# BV100011_ControlConnector.net
KiCad netlist of a schematic drawn in Altium Designer
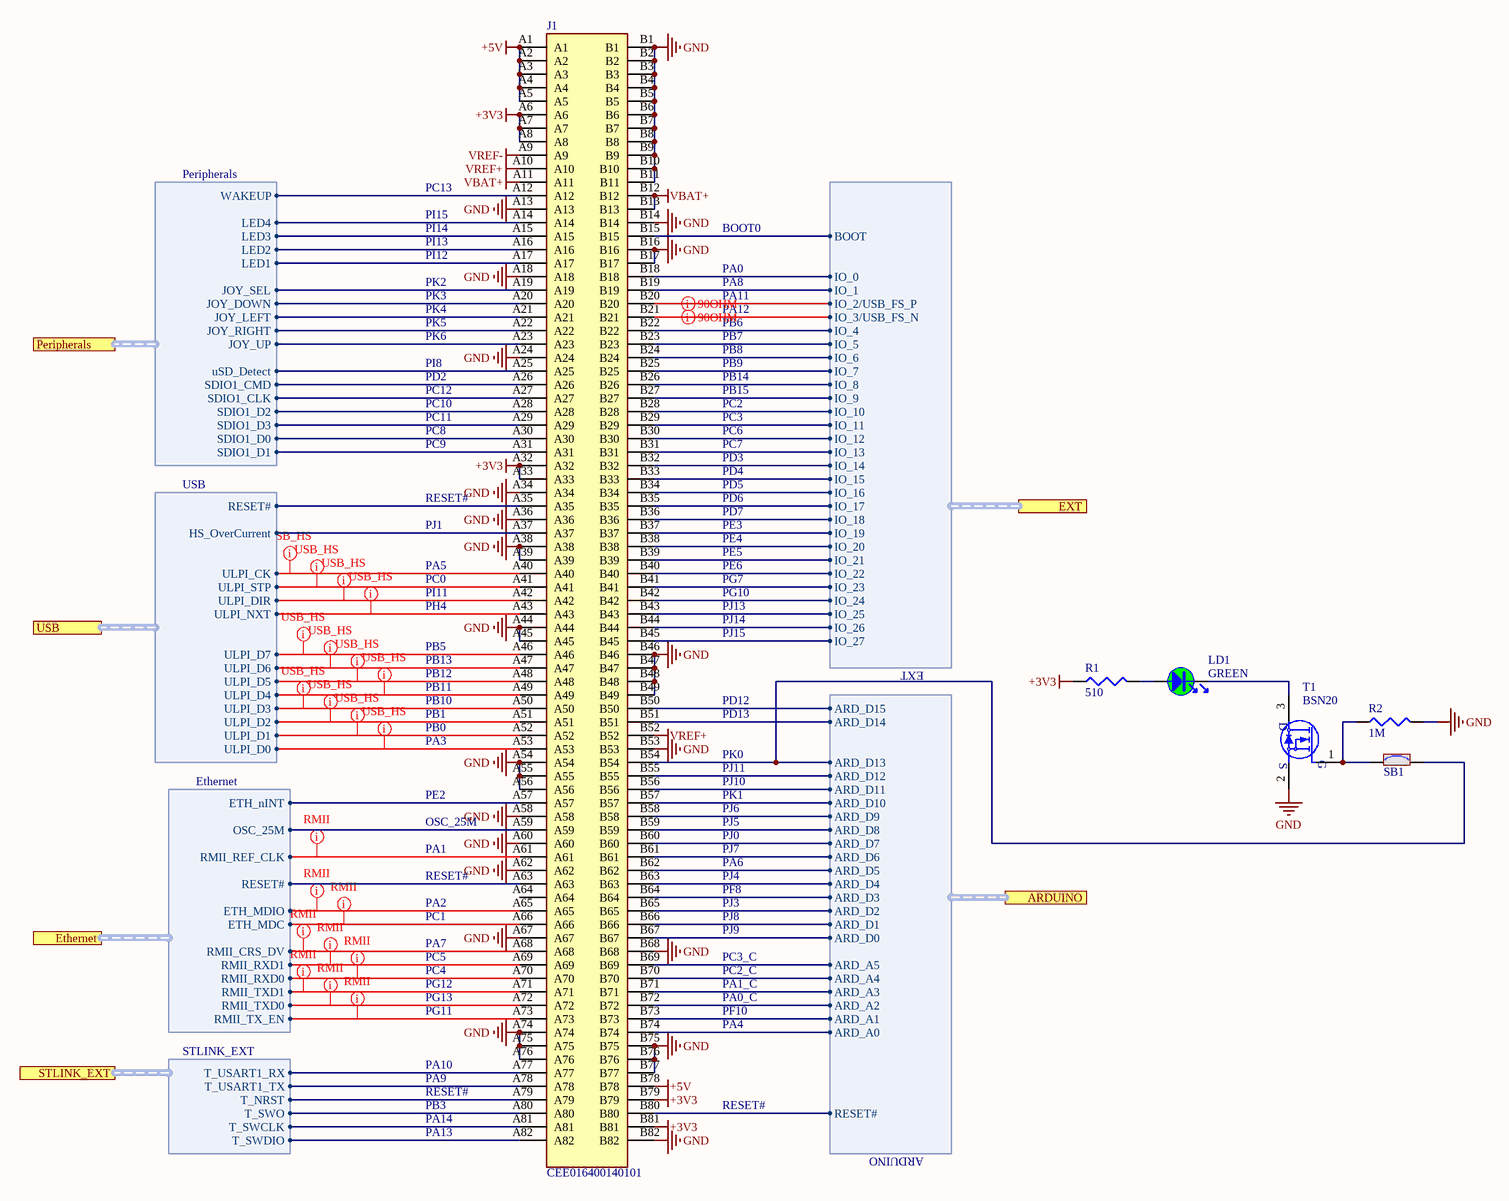
[diagram p0: BV100011_ControlConnector.SchDoc]

(export (version "E")
  (design (tool "Eeschema 10.0.6"))
  (components
    (comp (ref "J1")
      (value "CEE016400140101")
      (footprint "CEE016400140101-M")
      (description "Connector")
      (fields (field (name "MOUSER PART NUMBER") "523-CEE016400140101"))
      (libsource (lib "PCIE-164-02-F-D-RA") (part "CEE016400140101"))
    )
    (comp (ref "LD1")
      (value "GREEN")
      (footprint "LED_0603_GREEN")
      (description "LED, Green, 0603")
      (fields
        (field (name "INTERNAL_PART_NUMBER") "MCD-00050")
        (field (name "MANUFACTURER_PART_NUMBER") "19-213SYGC/S530-E2/TR8")
        (field (name "PROVIDED_BY") "Subcon")
      )
      (libsource (lib "MCD_PARTS_database") (part "LED_green"))
    )
    (comp (ref "R1")
      (value "510")
      (footprint "R0603")
      (description "Resistor")
      (fields (field (name "PUBLISHER") "Altium Limited"))
      (libsource (lib "Miscellaneous Devices") (part "Res3"))
    )
    (comp (ref "R2")
      (value "1M")
      (footprint "R0603")
      (description "Resistor")
      (fields (field (name "PUBLISHER") "Altium Limited"))
      (libsource (lib "Miscellaneous Devices") (part "Res3"))
    )
    (comp (ref "SB1")
      (value "SB_ON")
      (footprint "SB_0603")
      (description "Solder Bridge ON")
      (fields
        (field (name "INTERNAL_PART_NUMBER") "MCD-00071")
        (field (name "MANUFACTURER_PART_NUMBER") "RC0603JR-070RL")
        (field (name "PROVIDED_BY") "SUBCO")
      )
      (libsource (lib "MB1364") (part "MCD-00071"))
    )
    (comp (ref "T1")
      (value "BSN20")
      (footprint "MOS_SOT23")
      (description "N-channel enhancement mode field-effect transistor")
      (fields
        (field (name "INTERNAL_PART_NUMBER") "MCD-00151")
        (field (name "MANUFACTURER") "NXP")
        (field (name "PROVIDED_BY") "Subcon")
      )
      (libsource (lib "MCD_PARTS_database") (part "BSN20"))
    )
  )
  (nets
    (net (code "7") (name "+3V3") (class "Default")
      (node (ref "J1") (pin "A32") (pinfunction "A32_A32") (pintype "passive"))
      (node (ref "J1") (pin "A33") (pinfunction "A33_A33") (pintype "passive"))
      (node (ref "J1") (pin "A6") (pinfunction "A6_A6") (pintype "passive"))
      (node (ref "J1") (pin "A7") (pinfunction "A7_A7") (pintype "passive"))
      (node (ref "J1") (pin "A8") (pinfunction "A8_A8") (pintype "passive"))
      (node (ref "J1") (pin "B79") (pinfunction "B79_B79") (pintype "passive"))
      (node (ref "J1") (pin "B81") (pinfunction "B81_B81") (pintype "passive"))
      (node (ref "R1") (pin "1") (pinfunction "1_1") (pintype "passive"))
    )
    (net (code "8") (name "+5V") (class "Default")
      (node (ref "J1") (pin "A1") (pinfunction "A1_A1") (pintype "passive"))
      (node (ref "J1") (pin "A2") (pinfunction "A2_A2") (pintype "passive"))
      (node (ref "J1") (pin "A3") (pinfunction "A3_A3") (pintype "passive"))
      (node (ref "J1") (pin "A4") (pinfunction "A4_A4") (pintype "passive"))
      (node (ref "J1") (pin "A5") (pinfunction "A5_A5") (pintype "passive"))
      (node (ref "J1") (pin "B78") (pinfunction "B78_B78") (pintype "passive"))
    )
    (net (code "9") (name "/ARD_A0") (class "Default")
      (node (ref "J1") (pin "B74") (pinfunction "B74_B74") (pintype "passive"))
    )
    (net (code "10") (name "/ARD_A1") (class "Default")
      (node (ref "J1") (pin "B73") (pinfunction "B73_B73") (pintype "passive"))
    )
    (net (code "11") (name "/ARD_A2") (class "Default")
      (node (ref "J1") (pin "B72") (pinfunction "B72_B72") (pintype "passive"))
    )
    (net (code "12") (name "/ARD_A3") (class "Default")
      (node (ref "J1") (pin "B71") (pinfunction "B71_B71") (pintype "passive"))
    )
    (net (code "13") (name "/ARD_A4") (class "Default")
      (node (ref "J1") (pin "B70") (pinfunction "B70_B70") (pintype "passive"))
    )
    (net (code "14") (name "/ARD_A5") (class "Default")
      (node (ref "J1") (pin "B69") (pinfunction "B69_B69") (pintype "passive"))
    )
    (net (code "15") (name "/ARD_D0") (class "Default")
      (node (ref "J1") (pin "B67") (pinfunction "B67_B67") (pintype "passive"))
    )
    (net (code "16") (name "/ARD_D1") (class "Default")
      (node (ref "J1") (pin "B66") (pinfunction "B66_B66") (pintype "passive"))
    )
    (net (code "17") (name "/ARD_D2") (class "Default")
      (node (ref "J1") (pin "B65") (pinfunction "B65_B65") (pintype "passive"))
    )
    (net (code "18") (name "/ARD_D3") (class "Default")
      (node (ref "J1") (pin "B64") (pinfunction "B64_B64") (pintype "passive"))
    )
    (net (code "19") (name "/ARD_D4") (class "Default")
      (node (ref "J1") (pin "B63") (pinfunction "B63_B63") (pintype "passive"))
    )
    (net (code "20") (name "/ARD_D5") (class "Default")
      (node (ref "J1") (pin "B62") (pinfunction "B62_B62") (pintype "passive"))
    )
    (net (code "21") (name "/ARD_D6") (class "Default")
      (node (ref "J1") (pin "B61") (pinfunction "B61_B61") (pintype "passive"))
    )
    (net (code "22") (name "/ARD_D7") (class "Default")
      (node (ref "J1") (pin "B60") (pinfunction "B60_B60") (pintype "passive"))
    )
    (net (code "23") (name "/ARD_D8") (class "Default")
      (node (ref "J1") (pin "B59") (pinfunction "B59_B59") (pintype "passive"))
    )
    (net (code "24") (name "/ARD_D9") (class "Default")
      (node (ref "J1") (pin "B58") (pinfunction "B58_B58") (pintype "passive"))
    )
    (net (code "25") (name "/ARD_D10") (class "Default")
      (node (ref "J1") (pin "B57") (pinfunction "B57_B57") (pintype "passive"))
    )
    (net (code "26") (name "/ARD_D11") (class "Default")
      (node (ref "J1") (pin "B56") (pinfunction "B56_B56") (pintype "passive"))
    )
    (net (code "27") (name "/ARD_D12") (class "Default")
      (node (ref "J1") (pin "B55") (pinfunction "B55_B55") (pintype "passive"))
    )
    (net (code "28") (name "/ARD_D13") (class "Default")
      (node (ref "J1") (pin "B54") (pinfunction "B54_B54") (pintype "passive"))
      (node (ref "SB1") (pin "2") (pinfunction "2_2") (pintype "passive"))
    )
    (net (code "29") (name "/ARD_D14") (class "Default")
      (node (ref "J1") (pin "B51") (pinfunction "B51_B51") (pintype "passive"))
    )
    (net (code "30") (name "/ARD_D15") (class "Default")
      (node (ref "J1") (pin "B50") (pinfunction "B50_B50") (pintype "passive"))
    )
    (net (code "31") (name "/BOOT") (class "Default")
      (node (ref "J1") (pin "B15") (pinfunction "B15_B15") (pintype "passive"))
    )
    (net (code "32") (name "/ETH_MDC") (class "Default")
      (node (ref "J1") (pin "A66") (pinfunction "A66_A66") (pintype "passive"))
    )
    (net (code "33") (name "/ETH_MDIO") (class "Default")
      (node (ref "J1") (pin "A65") (pinfunction "A65_A65") (pintype "passive"))
    )
    (net (code "34") (name "/ETH_nINT") (class "Default")
      (node (ref "J1") (pin "A57") (pinfunction "A57_A57") (pintype "passive"))
    )
    (net (code "35") (name "/HS_OverCurrent") (class "Default")
      (node (ref "J1") (pin "A37") (pinfunction "A37_A37") (pintype "passive"))
    )
    (net (code "36") (name "/IO_0") (class "Default")
      (node (ref "J1") (pin "B18") (pinfunction "B18_B18") (pintype "passive"))
    )
    (net (code "37") (name "/IO_1") (class "Default")
      (node (ref "J1") (pin "B19") (pinfunction "B19_B19") (pintype "passive"))
    )
    (net (code "38") (name "/IO_2{slash}USB_FS_P") (class "Default")
      (node (ref "J1") (pin "B20") (pinfunction "B20_B20") (pintype "passive"))
    )
    (net (code "39") (name "/IO_3{slash}USB_FS_N") (class "Default")
      (node (ref "J1") (pin "B21") (pinfunction "B21_B21") (pintype "passive"))
    )
    (net (code "40") (name "/IO_4") (class "Default")
      (node (ref "J1") (pin "B22") (pinfunction "B22_B22") (pintype "passive"))
    )
    (net (code "41") (name "/IO_5") (class "Default")
      (node (ref "J1") (pin "B23") (pinfunction "B23_B23") (pintype "passive"))
    )
    (net (code "42") (name "/IO_6") (class "Default")
      (node (ref "J1") (pin "B24") (pinfunction "B24_B24") (pintype "passive"))
    )
    (net (code "43") (name "/IO_7") (class "Default")
      (node (ref "J1") (pin "B25") (pinfunction "B25_B25") (pintype "passive"))
    )
    (net (code "44") (name "/IO_8") (class "Default")
      (node (ref "J1") (pin "B26") (pinfunction "B26_B26") (pintype "passive"))
    )
    (net (code "45") (name "/IO_9") (class "Default")
      (node (ref "J1") (pin "B27") (pinfunction "B27_B27") (pintype "passive"))
    )
    (net (code "46") (name "/IO_10") (class "Default")
      (node (ref "J1") (pin "B28") (pinfunction "B28_B28") (pintype "passive"))
    )
    (net (code "47") (name "/IO_11") (class "Default")
      (node (ref "J1") (pin "B29") (pinfunction "B29_B29") (pintype "passive"))
    )
    (net (code "48") (name "/IO_12") (class "Default")
      (node (ref "J1") (pin "B30") (pinfunction "B30_B30") (pintype "passive"))
    )
    (net (code "49") (name "/IO_13") (class "Default")
      (node (ref "J1") (pin "B31") (pinfunction "B31_B31") (pintype "passive"))
    )
    (net (code "50") (name "/IO_14") (class "Default")
      (node (ref "J1") (pin "B32") (pinfunction "B32_B32") (pintype "passive"))
    )
    (net (code "51") (name "/IO_15") (class "Default")
      (node (ref "J1") (pin "B33") (pinfunction "B33_B33") (pintype "passive"))
    )
    (net (code "52") (name "/IO_16") (class "Default")
      (node (ref "J1") (pin "B34") (pinfunction "B34_B34") (pintype "passive"))
    )
    (net (code "53") (name "/IO_17") (class "Default")
      (node (ref "J1") (pin "B35") (pinfunction "B35_B35") (pintype "passive"))
    )
    (net (code "54") (name "/IO_18") (class "Default")
      (node (ref "J1") (pin "B36") (pinfunction "B36_B36") (pintype "passive"))
    )
    (net (code "55") (name "/IO_19") (class "Default")
      (node (ref "J1") (pin "B37") (pinfunction "B37_B37") (pintype "passive"))
    )
    (net (code "56") (name "/IO_20") (class "Default")
      (node (ref "J1") (pin "B38") (pinfunction "B38_B38") (pintype "passive"))
    )
    (net (code "57") (name "/IO_21") (class "Default")
      (node (ref "J1") (pin "B39") (pinfunction "B39_B39") (pintype "passive"))
    )
    (net (code "58") (name "/IO_22") (class "Default")
      (node (ref "J1") (pin "B40") (pinfunction "B40_B40") (pintype "passive"))
    )
    (net (code "59") (name "/IO_23") (class "Default")
      (node (ref "J1") (pin "B41") (pinfunction "B41_B41") (pintype "passive"))
    )
    (net (code "60") (name "/IO_24") (class "Default")
      (node (ref "J1") (pin "B42") (pinfunction "B42_B42") (pintype "passive"))
    )
    (net (code "61") (name "/IO_25") (class "Default")
      (node (ref "J1") (pin "B43") (pinfunction "B43_B43") (pintype "passive"))
    )
    (net (code "62") (name "/IO_26") (class "Default")
      (node (ref "J1") (pin "B44") (pinfunction "B44_B44") (pintype "passive"))
    )
    (net (code "63") (name "/IO_27") (class "Default")
      (node (ref "J1") (pin "B45") (pinfunction "B45_B45") (pintype "passive"))
    )
    (net (code "64") (name "/JOY_DOWN") (class "Default")
      (node (ref "J1") (pin "A20") (pinfunction "A20_A20") (pintype "passive"))
    )
    (net (code "65") (name "/JOY_LEFT") (class "Default")
      (node (ref "J1") (pin "A21") (pinfunction "A21_A21") (pintype "passive"))
    )
    (net (code "66") (name "/JOY_RIGHT") (class "Default")
      (node (ref "J1") (pin "A22") (pinfunction "A22_A22") (pintype "passive"))
    )
    (net (code "67") (name "/JOY_SEL") (class "Default")
      (node (ref "J1") (pin "A19") (pinfunction "A19_A19") (pintype "passive"))
    )
    (net (code "68") (name "/JOY_UP") (class "Default")
      (node (ref "J1") (pin "A23") (pinfunction "A23_A23") (pintype "passive"))
    )
    (net (code "69") (name "/LED1") (class "Default")
      (node (ref "J1") (pin "A17") (pinfunction "A17_A17") (pintype "passive"))
    )
    (net (code "70") (name "/LED2") (class "Default")
      (node (ref "J1") (pin "A16") (pinfunction "A16_A16") (pintype "passive"))
    )
    (net (code "71") (name "/LED3") (class "Default")
      (node (ref "J1") (pin "A15") (pinfunction "A15_A15") (pintype "passive"))
    )
    (net (code "72") (name "/LED4") (class "Default")
      (node (ref "J1") (pin "A14") (pinfunction "A14_A14") (pintype "passive"))
    )
    (net (code "73") (name "/OSC_25M") (class "Default")
      (node (ref "J1") (pin "A59") (pinfunction "A59_A59") (pintype "passive"))
    )
    (net (code "74") (name "/RMII_CRS_DV") (class "Default")
      (node (ref "J1") (pin "A68") (pinfunction "A68_A68") (pintype "passive"))
    )
    (net (code "75") (name "/RMII_REF_CLK") (class "Default")
      (node (ref "J1") (pin "A61") (pinfunction "A61_A61") (pintype "passive"))
    )
    (net (code "76") (name "/RMII_RXD0") (class "Default")
      (node (ref "J1") (pin "A70") (pinfunction "A70_A70") (pintype "passive"))
    )
    (net (code "77") (name "/RMII_RXD1") (class "Default")
      (node (ref "J1") (pin "A69") (pinfunction "A69_A69") (pintype "passive"))
    )
    (net (code "78") (name "/RMII_TXD0") (class "Default")
      (node (ref "J1") (pin "A72") (pinfunction "A72_A72") (pintype "passive"))
    )
    (net (code "79") (name "/RMII_TXD1") (class "Default")
      (node (ref "J1") (pin "A71") (pinfunction "A71_A71") (pintype "passive"))
    )
    (net (code "80") (name "/RMII_TX_EN") (class "Default")
      (node (ref "J1") (pin "A73") (pinfunction "A73_A73") (pintype "passive"))
    )
    (net (code "81") (name "/SDIO1_CLK") (class "Default")
      (node (ref "J1") (pin "A27") (pinfunction "A27_A27") (pintype "passive"))
    )
    (net (code "82") (name "/SDIO1_CMD") (class "Default")
      (node (ref "J1") (pin "A26") (pinfunction "A26_A26") (pintype "passive"))
    )
    (net (code "83") (name "/SDIO1_D0") (class "Default")
      (node (ref "J1") (pin "A30") (pinfunction "A30_A30") (pintype "passive"))
    )
    (net (code "84") (name "/SDIO1_D1") (class "Default")
      (node (ref "J1") (pin "A31") (pinfunction "A31_A31") (pintype "passive"))
    )
    (net (code "85") (name "/SDIO1_D2") (class "Default")
      (node (ref "J1") (pin "A28") (pinfunction "A28_A28") (pintype "passive"))
    )
    (net (code "86") (name "/SDIO1_D3") (class "Default")
      (node (ref "J1") (pin "A29") (pinfunction "A29_A29") (pintype "passive"))
    )
    (net (code "87") (name "/T_NRST") (class "Default")
      (node (ref "J1") (pin "A79") (pinfunction "A79_A79") (pintype "passive"))
    )
    (net (code "88") (name "/T_SWCLK") (class "Default")
      (node (ref "J1") (pin "A81") (pinfunction "A81_A81") (pintype "passive"))
    )
    (net (code "89") (name "/T_SWDIO") (class "Default")
      (node (ref "J1") (pin "A82") (pinfunction "A82_A82") (pintype "passive"))
    )
    (net (code "90") (name "/T_SWO") (class "Default")
      (node (ref "J1") (pin "A80") (pinfunction "A80_A80") (pintype "passive"))
    )
    (net (code "91") (name "/T_USART1_RX") (class "Default")
      (node (ref "J1") (pin "A77") (pinfunction "A77_A77") (pintype "passive"))
    )
    (net (code "92") (name "/T_USART1_TX") (class "Default")
      (node (ref "J1") (pin "A78") (pinfunction "A78_A78") (pintype "passive"))
    )
    (net (code "93") (name "/ULPI_CK") (class "Default")
      (node (ref "J1") (pin "A40") (pinfunction "A40_A40") (pintype "passive"))
    )
    (net (code "94") (name "/ULPI_D0") (class "Default")
      (node (ref "J1") (pin "A53") (pinfunction "A53_A53") (pintype "passive"))
    )
    (net (code "95") (name "/ULPI_D1") (class "Default")
      (node (ref "J1") (pin "A52") (pinfunction "A52_A52") (pintype "passive"))
    )
    (net (code "96") (name "/ULPI_D2") (class "Default")
      (node (ref "J1") (pin "A51") (pinfunction "A51_A51") (pintype "passive"))
    )
    (net (code "97") (name "/ULPI_D3") (class "Default")
      (node (ref "J1") (pin "A50") (pinfunction "A50_A50") (pintype "passive"))
    )
    (net (code "98") (name "/ULPI_D4") (class "Default")
      (node (ref "J1") (pin "A49") (pinfunction "A49_A49") (pintype "passive"))
    )
    (net (code "99") (name "/ULPI_D5") (class "Default")
      (node (ref "J1") (pin "A48") (pinfunction "A48_A48") (pintype "passive"))
    )
    (net (code "100") (name "/ULPI_D6") (class "Default")
      (node (ref "J1") (pin "A47") (pinfunction "A47_A47") (pintype "passive"))
    )
    (net (code "101") (name "/ULPI_D7") (class "Default")
      (node (ref "J1") (pin "A46") (pinfunction "A46_A46") (pintype "passive"))
    )
    (net (code "102") (name "/ULPI_DIR") (class "Default")
      (node (ref "J1") (pin "A42") (pinfunction "A42_A42") (pintype "passive"))
    )
    (net (code "103") (name "/ULPI_NXT") (class "Default")
      (node (ref "J1") (pin "A43") (pinfunction "A43_A43") (pintype "passive"))
    )
    (net (code "104") (name "/ULPI_STP") (class "Default")
      (node (ref "J1") (pin "A41") (pinfunction "A41_A41") (pintype "passive"))
    )
    (net (code "105") (name "/WAKEUP") (class "Default")
      (node (ref "J1") (pin "A12") (pinfunction "A12_A12") (pintype "passive"))
    )
    (net (code "106") (name "/uSD_Detect") (class "Default")
      (node (ref "J1") (pin "A25") (pinfunction "A25_A25") (pintype "passive"))
    )
    (net (code "113") (name "GND") (class "Default")
      (node (ref "J1") (pin "A13") (pinfunction "A13_A13") (pintype "passive"))
      (node (ref "J1") (pin "A18") (pinfunction "A18_A18") (pintype "passive"))
      (node (ref "J1") (pin "A24") (pinfunction "A24_A24") (pintype "passive"))
      (node (ref "J1") (pin "A34") (pinfunction "A34_A34") (pintype "passive"))
      (node (ref "J1") (pin "A36") (pinfunction "A36_A36") (pintype "passive"))
      (node (ref "J1") (pin "A38") (pinfunction "A38_A38") (pintype "passive"))
      (node (ref "J1") (pin "A39") (pinfunction "A39_A39") (pintype "passive"))
      (node (ref "J1") (pin "A44") (pinfunction "A44_A44") (pintype "passive"))
      (node (ref "J1") (pin "A45") (pinfunction "A45_A45") (pintype "passive"))
      (node (ref "J1") (pin "A54") (pinfunction "A54_A54") (pintype "passive"))
      (node (ref "J1") (pin "A55") (pinfunction "A55_A55") (pintype "passive"))
      (node (ref "J1") (pin "A56") (pinfunction "A56_A56") (pintype "passive"))
      (node (ref "J1") (pin "A58") (pinfunction "A58_A58") (pintype "passive"))
      (node (ref "J1") (pin "A60") (pinfunction "A60_A60") (pintype "passive"))
      (node (ref "J1") (pin "A62") (pinfunction "A62_A62") (pintype "passive"))
      (node (ref "J1") (pin "A67") (pinfunction "A67_A67") (pintype "passive"))
      (node (ref "J1") (pin "A74") (pinfunction "A74_A74") (pintype "passive"))
      (node (ref "J1") (pin "A75") (pinfunction "A75_A75") (pintype "passive"))
      (node (ref "J1") (pin "A76") (pinfunction "A76_A76") (pintype "passive"))
      (node (ref "J1") (pin "B1") (pinfunction "B1_B1") (pintype "passive"))
      (node (ref "J1") (pin "B10") (pinfunction "B10_B10") (pintype "passive"))
      (node (ref "J1") (pin "B11") (pinfunction "B11_B11") (pintype "passive"))
      (node (ref "J1") (pin "B14") (pinfunction "B14_B14") (pintype "passive"))
      (node (ref "J1") (pin "B16") (pinfunction "B16_B16") (pintype "passive"))
      (node (ref "J1") (pin "B17") (pinfunction "B17_B17") (pintype "passive"))
      (node (ref "J1") (pin "B2") (pinfunction "B2_B2") (pintype "passive"))
      (node (ref "J1") (pin "B3") (pinfunction "B3_B3") (pintype "passive"))
      (node (ref "J1") (pin "B4") (pinfunction "B4_B4") (pintype "passive"))
      (node (ref "J1") (pin "B46") (pinfunction "B46_B46") (pintype "passive"))
      (node (ref "J1") (pin "B47") (pinfunction "B47_B47") (pintype "passive"))
      (node (ref "J1") (pin "B48") (pinfunction "B48_B48") (pintype "passive"))
      (node (ref "J1") (pin "B49") (pinfunction "B49_B49") (pintype "passive"))
      (node (ref "J1") (pin "B5") (pinfunction "B5_B5") (pintype "passive"))
      (node (ref "J1") (pin "B53") (pinfunction "B53_B53") (pintype "passive"))
      (node (ref "J1") (pin "B6") (pinfunction "B6_B6") (pintype "passive"))
      (node (ref "J1") (pin "B68") (pinfunction "B68_B68") (pintype "passive"))
      (node (ref "J1") (pin "B7") (pinfunction "B7_B7") (pintype "passive"))
      (node (ref "J1") (pin "B75") (pinfunction "B75_B75") (pintype "passive"))
      (node (ref "J1") (pin "B76") (pinfunction "B76_B76") (pintype "passive"))
      (node (ref "J1") (pin "B77") (pinfunction "B77_B77") (pintype "passive"))
      (node (ref "J1") (pin "B8") (pinfunction "B8_B8") (pintype "passive"))
      (node (ref "J1") (pin "B82") (pinfunction "B82_B82") (pintype "passive"))
      (node (ref "J1") (pin "B9") (pinfunction "B9_B9") (pintype "passive"))
      (node (ref "R2") (pin "2") (pinfunction "2_2") (pintype "passive"))
      (node (ref "T1") (pin "2") (pinfunction "S_2") (pintype "passive"))
    )
    (net (code "114") (name "Net-(LD1-Pad1)") (class "Default")
      (node (ref "LD1") (pin "1") (pintype "passive"))
      (node (ref "R1") (pin "2") (pinfunction "2_2") (pintype "passive"))
    )
    (net (code "115") (name "Net-(T1-D)") (class "Default")
      (node (ref "LD1") (pin "2") (pintype "passive"))
      (node (ref "T1") (pin "3") (pinfunction "D_3") (pintype "passive"))
    )
    (net (code "116") (name "Net-(T1-G)") (class "Default")
      (node (ref "R2") (pin "1") (pinfunction "1_1") (pintype "passive"))
      (node (ref "SB1") (pin "1") (pinfunction "1_1") (pintype "passive"))
      (node (ref "T1") (pin "1") (pinfunction "G_1") (pintype "passive"))
    )
    (net (code "117") (name "VBAT+") (class "Default")
      (node (ref "J1") (pin "A11") (pinfunction "A11_A11") (pintype "passive"))
      (node (ref "J1") (pin "B12") (pinfunction "B12_B12") (pintype "passive"))
      (node (ref "J1") (pin "B13") (pinfunction "B13_B13") (pintype "passive"))
    )
    (net (code "118") (name "VREF+") (class "Default")
      (node (ref "J1") (pin "A10") (pinfunction "A10_A10") (pintype "passive"))
      (node (ref "J1") (pin "B52") (pinfunction "B52_B52") (pintype "passive"))
    )
    (net (code "119") (name "VREF-") (class "Default")
      (node (ref "J1") (pin "A9") (pinfunction "A9_A9") (pintype "passive"))
    )
    (net (code "120") (name "unconnected-(J1-PadA35)") (class "Default")
      (node (ref "J1") (pin "A35") (pinfunction "A35_A35") (pintype "passive"))
    )
    (net (code "121") (name "unconnected-(J1-PadA63)") (class "Default")
      (node (ref "J1") (pin "A63") (pinfunction "A63_A63") (pintype "passive"))
    )
    (net (code "122") (name "unconnected-(J1-PadA64)") (class "Default")
      (node (ref "J1") (pin "A64") (pinfunction "A64_A64") (pintype "passive"))
    )
    (net (code "123") (name "unconnected-(J1-PadB80)") (class "Default")
      (node (ref "J1") (pin "B80") (pinfunction "B80_B80") (pintype "passive"))
    )
  )
)
